# RK3566_USB_GPIO.net
KiCad netlist of a schematic drawn in Altium Designer
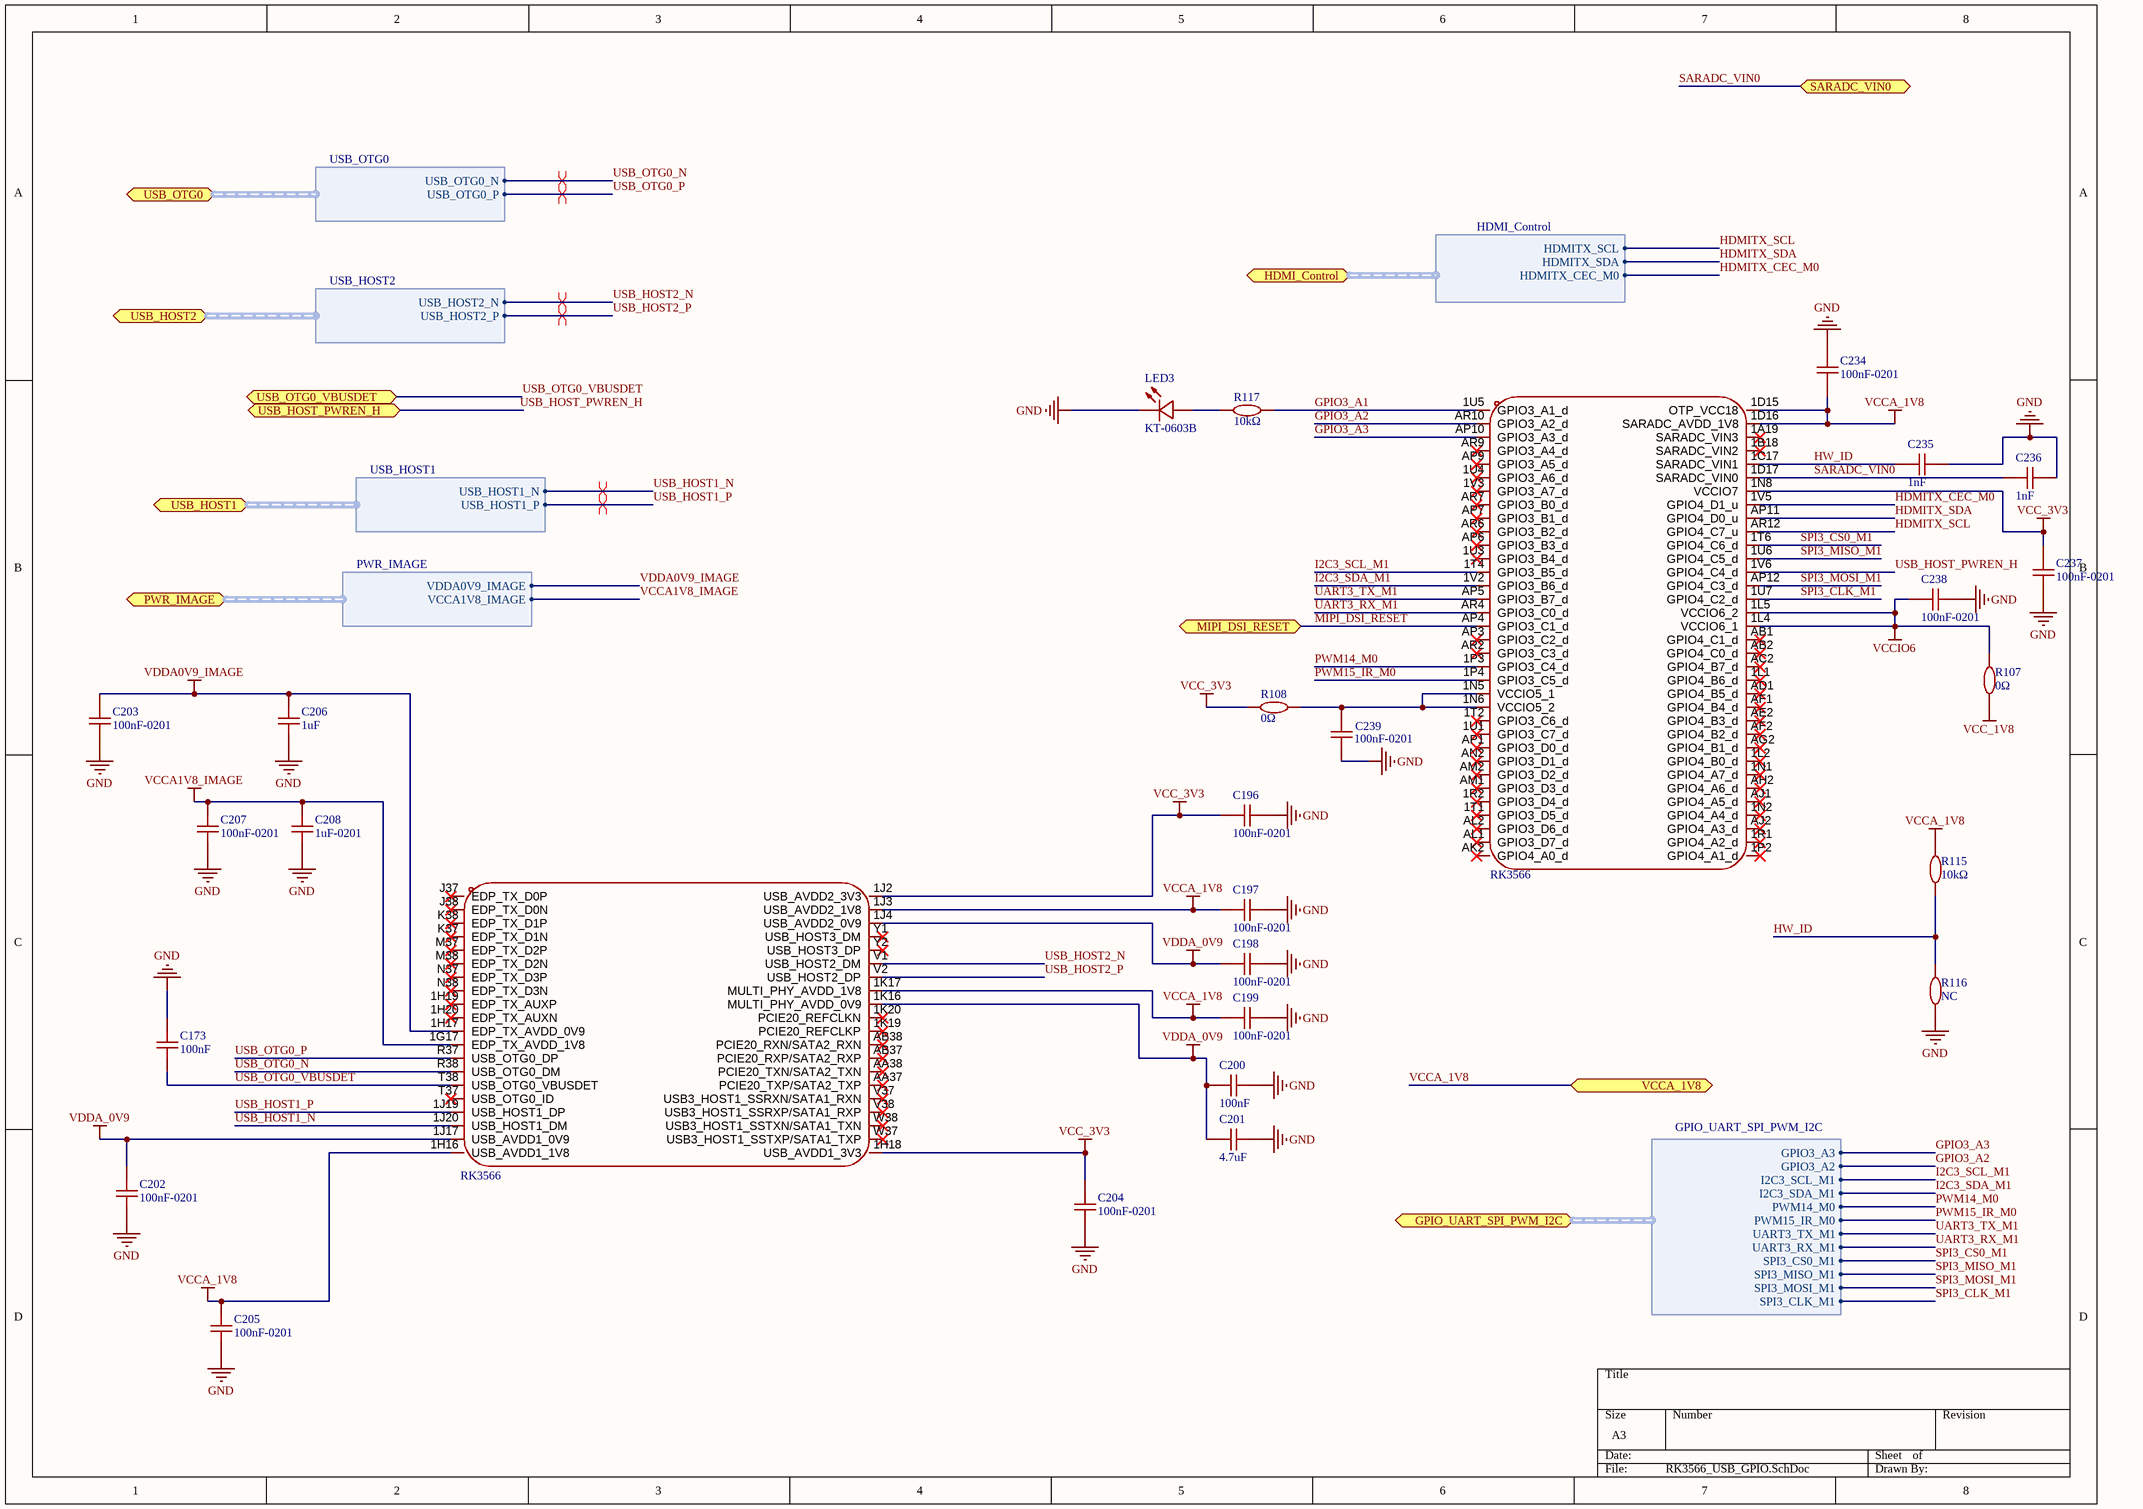
[diagram p0: RK3566_USB_GPIO.SchDoc]

(export (version "E")
  (design (tool "Eeschema 10.0.6"))
  (components
    (comp (ref "C173")
      (value "100nF")
      (footprint "C0402")
      (description "50V 100nF X7R ±10% 0402 Ceramic Capacitors ROHS")
      (libsource (lib "RLC") (part "100nF"))
    )
    (comp (ref "C196")
      (value "100nF-0201")
      (footprint "C0201")
      (description "CL03A104KO3NNNC")
      (libsource (lib "RLC") (part "100nF-0201"))
    )
    (comp (ref "C197")
      (value "100nF-0201")
      (footprint "C0201")
      (description "CL03A104KO3NNNC")
      (libsource (lib "RLC") (part "100nF-0201"))
    )
    (comp (ref "C198")
      (value "100nF-0201")
      (footprint "C0201")
      (description "CL03A104KO3NNNC")
      (libsource (lib "RLC") (part "100nF-0201"))
    )
    (comp (ref "C199")
      (value "100nF-0201")
      (footprint "C0201")
      (description "CL03A104KO3NNNC")
      (libsource (lib "RLC") (part "100nF-0201"))
    )
    (comp (ref "C200")
      (value "100nF")
      (footprint "C0402")
      (description "50V 100nF X7R ±10% 0402 Ceramic Capacitors ROHS")
      (libsource (lib "RLC") (part "100nF"))
    )
    (comp (ref "C201")
      (value "4.7uF")
      (footprint "C0402")
      (description "10V 4.7uF X5R ±20% 0402 Ceramic Capacitors ROHS")
      (libsource (lib "RLC") (part "4.7uF"))
    )
    (comp (ref "C202")
      (value "100nF-0201")
      (footprint "C0201")
      (description "CL03A104KO3NNNC")
      (libsource (lib "RLC") (part "100nF-0201"))
    )
    (comp (ref "C203")
      (value "100nF-0201")
      (footprint "C0201")
      (description "CL03A104KO3NNNC")
      (libsource (lib "RLC") (part "100nF-0201"))
    )
    (comp (ref "C204")
      (value "100nF-0201")
      (footprint "C0201")
      (description "CL03A104KO3NNNC")
      (libsource (lib "RLC") (part "100nF-0201"))
    )
    (comp (ref "C205")
      (value "100nF-0201")
      (footprint "C0201")
      (description "CL03A104KO3NNNC")
      (libsource (lib "RLC") (part "100nF-0201"))
    )
    (comp (ref "C206")
      (value "1uF")
      (footprint "C0402")
      (description "50V 1uF X5R ±10% 0402 Ceramic Capacitors ROHS")
      (libsource (lib "RLC") (part "1uF"))
    )
    (comp (ref "C207")
      (value "100nF-0201")
      (footprint "C0201")
      (description "CL03A104KO3NNNC")
      (libsource (lib "RLC") (part "100nF-0201"))
    )
    (comp (ref "C208")
      (value "1uF-0201")
      (footprint "C0201")
      (description "CL03A104KO3NNNC")
      (libsource (lib "RLC") (part "1uF-0201"))
    )
    (comp (ref "C234")
      (value "100nF-0201")
      (footprint "C0201")
      (description "CL03A104KO3NNNC")
      (libsource (lib "RLC") (part "100nF-0201"))
    )
    (comp (ref "C235")
      (value "1nF")
      (footprint "C0402")
      (description "50V 1nF X7R ±10% 0402 Ceramic Capacitors ROHS")
      (libsource (lib "RLC") (part "1nF"))
    )
    (comp (ref "C236")
      (value "1nF")
      (footprint "C0402")
      (description "50V 1nF X7R ±10% 0402 Ceramic Capacitors ROHS")
      (libsource (lib "RLC") (part "1nF"))
    )
    (comp (ref "C237")
      (value "100nF-0201")
      (footprint "C0201")
      (description "CL03A104KO3NNNC")
      (libsource (lib "RLC") (part "100nF-0201"))
    )
    (comp (ref "C238")
      (value "100nF-0201")
      (footprint "C0201")
      (description "CL03A104KO3NNNC")
      (libsource (lib "RLC") (part "100nF-0201"))
    )
    (comp (ref "C239")
      (value "100nF-0201")
      (footprint "C0201")
      (description "CL03A104KO3NNNC")
      (libsource (lib "RLC") (part "100nF-0201"))
    )
    (comp (ref "LED3")
      (value "KT-0603B")
      (footprint "LED0603-BL")
      (description "30mA 2.6V~3.2V Blue 0603 LED Indication - Discrete ROHS")
      (libsource (lib "LED") (part "KT-0603B"))
    )
    (comp (ref "R107")
      (value "0Ω")
      (footprint "R0402")
      (description "0Ω 62.5mW 50V Thick Film Resistor ±1% 0402 Chip Resistor - Surface Mount ROHS")
      (libsource (lib "RLC") (part "0Ω"))
    )
    (comp (ref "R108")
      (value "0Ω")
      (footprint "R0402")
      (description "0Ω 62.5mW 50V Thick Film Resistor ±1% 0402 Chip Resistor - Surface Mount ROHS")
      (libsource (lib "RLC") (part "0Ω"))
    )
    (comp (ref "R115")
      (value "10kΩ")
      (footprint "R0402")
      (description "62.5mW 10kΩ 50V ±100ppm/℃ Thick Film Resistor ±1% 0402 Chip Resistor - Surface Mount ROHS")
      (libsource (lib "RLC") (part "10kΩ"))
    )
    (comp (ref "R116")
      (value "NC")
      (footprint "R0402")
      (description "62.5mW 10kΩ 50V ±100ppm/℃ Thick Film Resistor ±1% 0402 Chip Resistor - Surface Mount ROHS")
      (libsource (lib "RLC") (part "10kΩ"))
    )
    (comp (ref "R117")
      (value "10kΩ")
      (footprint "R0402")
      (description "62.5mW 10kΩ 50V ±100ppm/℃ Thick Film Resistor ±1% 0402 Chip Resistor - Surface Mount ROHS")
      (libsource (lib "RLC") (part "10kΩ"))
    )
    (comp (ref "U2")
      (value "RK3566")
      (footprint "BGA-565_L15.5-W14.4-P0.40_RK3566_1")
      (description "BGA-565(15.5x14.4)")
      (libsource (lib "IC") (part "RK3566"))
    )
  )
  (nets
    (net (code "7") (name "/GPIO3_A1") (class "Default")
      (node (ref "R117") (pin "1") (pinfunction "1_1") (pintype "passive"))
      (node (ref "U2") (pin "1U5") (pinfunction "GPIO3_A1_d_1U5") (pintype "passive"))
    )
    (net (code "8") (name "/GPIO3_A2") (class "Default")
      (node (ref "U2") (pin "AR10") (pinfunction "GPIO3_A2_d_AR10") (pintype "passive"))
    )
    (net (code "9") (name "/GPIO3_A3") (class "Default")
      (node (ref "U2") (pin "AP10") (pinfunction "GPIO3_A3_d_AP10") (pintype "passive"))
    )
    (net (code "10") (name "/HDMITX_CEC_M0") (class "Default")
      (node (ref "U2") (pin "1V5") (pinfunction "GPIO4_D1_u_1V5") (pintype "passive"))
    )
    (net (code "11") (name "/HDMITX_SCL") (class "Default")
      (node (ref "U2") (pin "AR12") (pinfunction "GPIO4_C7_u_AR12") (pintype "passive"))
    )
    (net (code "12") (name "/HDMITX_SDA") (class "Default")
      (node (ref "U2") (pin "AP11") (pinfunction "GPIO4_D0_u_AP11") (pintype "passive"))
    )
    (net (code "13") (name "/HW_ID") (class "Default")
      (node (ref "C235") (pin "1") (pinfunction "1_1") (pintype "passive"))
      (node (ref "R115") (pin "1") (pinfunction "1_1") (pintype "passive"))
      (node (ref "R116") (pin "2") (pinfunction "2_2") (pintype "passive"))
      (node (ref "U2") (pin "1C17") (pinfunction "SARADC_VIN1_1C17") (pintype "passive"))
    )
    (net (code "14") (name "/I2C3_SCL_M1") (class "Default")
      (node (ref "U2") (pin "1T4") (pinfunction "GPIO3_B5_d_1T4") (pintype "passive"))
    )
    (net (code "15") (name "/I2C3_SDA_M1") (class "Default")
      (node (ref "U2") (pin "1V2") (pinfunction "GPIO3_B6_d_1V2") (pintype "passive"))
    )
    (net (code "16") (name "/MIPI_DSI_RESET") (class "Default")
      (node (ref "U2") (pin "AP4") (pinfunction "GPIO3_C1_d_AP4") (pintype "passive"))
    )
    (net (code "17") (name "/PWM14_M0") (class "Default")
      (node (ref "U2") (pin "1P3") (pinfunction "GPIO3_C4_d_1P3") (pintype "passive"))
    )
    (net (code "18") (name "/PWM15_IR_M0") (class "Default")
      (node (ref "U2") (pin "1P4") (pinfunction "GPIO3_C5_d_1P4") (pintype "passive"))
    )
    (net (code "19") (name "/SARADC_VIN0") (class "Default")
      (node (ref "C236") (pin "1") (pinfunction "1_1") (pintype "passive"))
      (node (ref "U2") (pin "1D17") (pinfunction "SARADC_VIN0_1D17") (pintype "passive"))
    )
    (net (code "20") (name "/SPI3_CLK_M1") (class "Default")
      (node (ref "U2") (pin "1U7") (pinfunction "GPIO4_C2_d_1U7") (pintype "passive"))
    )
    (net (code "21") (name "/SPI3_CS0_M1") (class "Default")
      (node (ref "U2") (pin "1T6") (pinfunction "GPIO4_C6_d_1T6") (pintype "passive"))
    )
    (net (code "22") (name "/SPI3_MISO_M1") (class "Default")
      (node (ref "U2") (pin "1U6") (pinfunction "GPIO4_C5_d_1U6") (pintype "passive"))
    )
    (net (code "23") (name "/SPI3_MOSI_M1") (class "Default")
      (node (ref "U2") (pin "AP12") (pinfunction "GPIO4_C3_d_AP12") (pintype "passive"))
    )
    (net (code "24") (name "/UART3_RX_M1") (class "Default")
      (node (ref "U2") (pin "AR4") (pinfunction "GPIO3_C0_d_AR4") (pintype "passive"))
    )
    (net (code "25") (name "/UART3_TX_M1") (class "Default")
      (node (ref "U2") (pin "AP5") (pinfunction "GPIO3_B7_d_AP5") (pintype "passive"))
    )
    (net (code "26") (name "/USB_HOST1_N") (class "Default")
      (node (ref "U2") (pin "1J20") (pinfunction "USB_HOST1_DM_1J20") (pintype "passive"))
    )
    (net (code "27") (name "/USB_HOST1_P") (class "Default")
      (node (ref "U2") (pin "1J19") (pinfunction "USB_HOST1_DP_1J19") (pintype "passive"))
    )
    (net (code "28") (name "/USB_HOST2_N") (class "Default")
      (node (ref "U2") (pin "V1") (pinfunction "USB_HOST2_DM_V1") (pintype "passive"))
    )
    (net (code "29") (name "/USB_HOST2_P") (class "Default")
      (node (ref "U2") (pin "V2") (pinfunction "USB_HOST2_DP_V2") (pintype "passive"))
    )
    (net (code "30") (name "/USB_HOST_PWREN_H") (class "Default")
      (node (ref "U2") (pin "1V6") (pinfunction "GPIO4_C4_d_1V6") (pintype "passive"))
    )
    (net (code "31") (name "/USB_OTG0_N") (class "Default")
      (node (ref "U2") (pin "R38") (pinfunction "USB_OTG0_DM_R38") (pintype "passive"))
    )
    (net (code "32") (name "/USB_OTG0_P") (class "Default")
      (node (ref "U2") (pin "R37") (pinfunction "USB_OTG0_DP_R37") (pintype "passive"))
    )
    (net (code "33") (name "/USB_OTG0_VBUSDET") (class "Default")
      (node (ref "C173") (pin "1") (pinfunction "1_1") (pintype "passive"))
      (node (ref "U2") (pin "T38") (pinfunction "USB_OTG0_VBUSDET_T38") (pintype "passive"))
    )
    (net (code "40") (name "GND") (class "Default")
      (node (ref "C173") (pin "2") (pinfunction "2_2") (pintype "passive"))
      (node (ref "C196") (pin "2") (pinfunction "2_2") (pintype "passive"))
      (node (ref "C197") (pin "2") (pinfunction "2_2") (pintype "passive"))
      (node (ref "C198") (pin "2") (pinfunction "2_2") (pintype "passive"))
      (node (ref "C199") (pin "2") (pinfunction "2_2") (pintype "passive"))
      (node (ref "C200") (pin "2") (pinfunction "2_2") (pintype "passive"))
      (node (ref "C201") (pin "2") (pinfunction "2_2") (pintype "passive"))
      (node (ref "C202") (pin "1") (pinfunction "1_1") (pintype "passive"))
      (node (ref "C203") (pin "1") (pinfunction "1_1") (pintype "passive"))
      (node (ref "C204") (pin "1") (pinfunction "1_1") (pintype "passive"))
      (node (ref "C205") (pin "1") (pinfunction "1_1") (pintype "passive"))
      (node (ref "C206") (pin "1") (pinfunction "1_1") (pintype "passive"))
      (node (ref "C207") (pin "1") (pinfunction "1_1") (pintype "passive"))
      (node (ref "C208") (pin "1") (pinfunction "1_1") (pintype "passive"))
      (node (ref "C234") (pin "1") (pinfunction "1_1") (pintype "passive"))
      (node (ref "C235") (pin "2") (pinfunction "2_2") (pintype "passive"))
      (node (ref "C236") (pin "2") (pinfunction "2_2") (pintype "passive"))
      (node (ref "C237") (pin "2") (pinfunction "2_2") (pintype "passive"))
      (node (ref "C238") (pin "2") (pinfunction "2_2") (pintype "passive"))
      (node (ref "C239") (pin "1") (pinfunction "1_1") (pintype "passive"))
      (node (ref "LED3") (pin "1") (pinfunction "K_1") (pintype "passive"))
      (node (ref "R116") (pin "1") (pinfunction "1_1") (pintype "passive"))
    )
    (net (code "41") (name "Net-(LED3-A)") (class "Default")
      (node (ref "LED3") (pin "2") (pinfunction "A_2") (pintype "passive"))
      (node (ref "R117") (pin "2") (pinfunction "2_2") (pintype "passive"))
    )
    (net (code "42") (name "Net-(U2F-VCCIO5_1)") (class "Default")
      (node (ref "C239") (pin "2") (pinfunction "2_2") (pintype "passive"))
      (node (ref "R108") (pin "2") (pinfunction "2_2") (pintype "passive"))
      (node (ref "U2") (pin "1N5") (pinfunction "VCCIO5_1_1N5") (pintype "passive"))
      (node (ref "U2") (pin "1N6") (pinfunction "VCCIO5_2_1N6") (pintype "passive"))
    )
    (net (code "43") (name "VCCA1V8_IMAGE") (class "Default")
      (node (ref "C207") (pin "2") (pinfunction "2_2") (pintype "passive"))
      (node (ref "C208") (pin "2") (pinfunction "2_2") (pintype "passive"))
      (node (ref "U2") (pin "1G17") (pinfunction "EDP_TX_AVDD_1V8_1G17") (pintype "passive"))
    )
    (net (code "44") (name "VCCA_1V8") (class "Default")
      (node (ref "C197") (pin "1") (pinfunction "1_1") (pintype "passive"))
      (node (ref "C199") (pin "1") (pinfunction "1_1") (pintype "passive"))
      (node (ref "C205") (pin "2") (pinfunction "2_2") (pintype "passive"))
      (node (ref "C234") (pin "2") (pinfunction "2_2") (pintype "passive"))
      (node (ref "R115") (pin "2") (pinfunction "2_2") (pintype "passive"))
      (node (ref "U2") (pin "1D15") (pinfunction "OTP_VCC18_1D15") (pintype "passive"))
      (node (ref "U2") (pin "1D16") (pinfunction "SARADC_AVDD_1V8_1D16") (pintype "passive"))
      (node (ref "U2") (pin "1H16") (pinfunction "USB_AVDD1_1V8_1H16") (pintype "passive"))
      (node (ref "U2") (pin "1J3") (pinfunction "USB_AVDD2_1V8_1J3") (pintype "passive"))
      (node (ref "U2") (pin "1K17") (pinfunction "MULTI_PHY_AVDD_1V8_1K17") (pintype "passive"))
    )
    (net (code "45") (name "VCCIO6") (class "Default")
      (node (ref "C238") (pin "1") (pinfunction "1_1") (pintype "passive"))
      (node (ref "R107") (pin "2") (pinfunction "2_2") (pintype "passive"))
      (node (ref "U2") (pin "1L4") (pinfunction "VCCIO6_1_1L4") (pintype "passive"))
      (node (ref "U2") (pin "1L5") (pinfunction "VCCIO6_2_1L5") (pintype "passive"))
    )
    (net (code "46") (name "VCC_1V8") (class "Default")
      (node (ref "R107") (pin "1") (pinfunction "1_1") (pintype "passive"))
    )
    (net (code "47") (name "VCC_3V3") (class "Default")
      (node (ref "C196") (pin "1") (pinfunction "1_1") (pintype "passive"))
      (node (ref "C204") (pin "2") (pinfunction "2_2") (pintype "passive"))
      (node (ref "C237") (pin "1") (pinfunction "1_1") (pintype "passive"))
      (node (ref "R108") (pin "1") (pinfunction "1_1") (pintype "passive"))
      (node (ref "U2") (pin "1H18") (pinfunction "USB_AVDD1_3V3_1H18") (pintype "passive"))
      (node (ref "U2") (pin "1J2") (pinfunction "USB_AVDD2_3V3_1J2") (pintype "passive"))
      (node (ref "U2") (pin "1N8") (pinfunction "VCCIO7_1N8") (pintype "passive"))
    )
    (net (code "48") (name "VDDA0V9_IMAGE") (class "Default")
      (node (ref "C203") (pin "2") (pinfunction "2_2") (pintype "passive"))
      (node (ref "C206") (pin "2") (pinfunction "2_2") (pintype "passive"))
      (node (ref "U2") (pin "1H17") (pinfunction "EDP_TX_AVDD_0V9_1H17") (pintype "passive"))
    )
    (net (code "49") (name "VDDA_0V9") (class "Default")
      (node (ref "C198") (pin "1") (pinfunction "1_1") (pintype "passive"))
      (node (ref "C200") (pin "1") (pinfunction "1_1") (pintype "passive"))
      (node (ref "C201") (pin "1") (pinfunction "1_1") (pintype "passive"))
      (node (ref "C202") (pin "2") (pinfunction "2_2") (pintype "passive"))
      (node (ref "U2") (pin "1J17") (pinfunction "USB_AVDD1_0V9_1J17") (pintype "passive"))
      (node (ref "U2") (pin "1J4") (pinfunction "USB_AVDD2_0V9_1J4") (pintype "passive"))
      (node (ref "U2") (pin "1K16") (pinfunction "MULTI_PHY_AVDD_0V9_1K16") (pintype "passive"))
    )
    (net (code "50") (name "unconnected-(U2F-GPIO3_A4_d-PadAR9)") (class "Default")
      (node (ref "U2") (pin "AR9") (pinfunction "GPIO3_A4_d_AR9") (pintype "passive+no_connect"))
    )
    (net (code "51") (name "unconnected-(U2F-GPIO3_A5_d-PadAP9)") (class "Default")
      (node (ref "U2") (pin "AP9") (pinfunction "GPIO3_A5_d_AP9") (pintype "passive+no_connect"))
    )
    (net (code "52") (name "unconnected-(U2F-GPIO3_A6_d-Pad1U4)") (class "Default")
      (node (ref "U2") (pin "1U4") (pinfunction "GPIO3_A6_d_1U4") (pintype "passive+no_connect"))
    )
    (net (code "53") (name "unconnected-(U2F-GPIO3_A7_d-Pad1V3)") (class "Default")
      (node (ref "U2") (pin "1V3") (pinfunction "GPIO3_A7_d_1V3") (pintype "passive+no_connect"))
    )
    (net (code "54") (name "unconnected-(U2F-GPIO3_B0_d-PadAR7)") (class "Default")
      (node (ref "U2") (pin "AR7") (pinfunction "GPIO3_B0_d_AR7") (pintype "passive+no_connect"))
    )
    (net (code "55") (name "unconnected-(U2F-GPIO3_B1_d-PadAP7)") (class "Default")
      (node (ref "U2") (pin "AP7") (pinfunction "GPIO3_B1_d_AP7") (pintype "passive+no_connect"))
    )
    (net (code "56") (name "unconnected-(U2F-GPIO3_B2_d-PadAR6)") (class "Default")
      (node (ref "U2") (pin "AR6") (pinfunction "GPIO3_B2_d_AR6") (pintype "passive+no_connect"))
    )
    (net (code "57") (name "unconnected-(U2F-GPIO3_B3_d-PadAP6)") (class "Default")
      (node (ref "U2") (pin "AP6") (pinfunction "GPIO3_B3_d_AP6") (pintype "passive+no_connect"))
    )
    (net (code "58") (name "unconnected-(U2F-GPIO3_B4_d-Pad1U3)") (class "Default")
      (node (ref "U2") (pin "1U3") (pinfunction "GPIO3_B4_d_1U3") (pintype "passive+no_connect"))
    )
    (net (code "59") (name "unconnected-(U2F-GPIO3_C2_d-PadAP3)") (class "Default")
      (node (ref "U2") (pin "AP3") (pinfunction "GPIO3_C2_d_AP3") (pintype "passive+no_connect"))
    )
    (net (code "60") (name "unconnected-(U2F-GPIO3_C3_d-PadAR2)") (class "Default")
      (node (ref "U2") (pin "AR2") (pinfunction "GPIO3_C3_d_AR2") (pintype "passive+no_connect"))
    )
    (net (code "61") (name "unconnected-(U2F-GPIO3_C6_d-Pad1T2)") (class "Default")
      (node (ref "U2") (pin "1T2") (pinfunction "GPIO3_C6_d_1T2") (pintype "passive+no_connect"))
    )
    (net (code "62") (name "unconnected-(U2F-GPIO3_C7_d-Pad1U1)") (class "Default")
      (node (ref "U2") (pin "1U1") (pinfunction "GPIO3_C7_d_1U1") (pintype "passive+no_connect"))
    )
    (net (code "63") (name "unconnected-(U2F-GPIO3_D0_d-PadAP1)") (class "Default")
      (node (ref "U2") (pin "AP1") (pinfunction "GPIO3_D0_d_AP1") (pintype "passive+no_connect"))
    )
    (net (code "64") (name "unconnected-(U2F-GPIO3_D1_d-PadAN2)") (class "Default")
      (node (ref "U2") (pin "AN2") (pinfunction "GPIO3_D1_d_AN2") (pintype "passive+no_connect"))
    )
    (net (code "65") (name "unconnected-(U2F-GPIO3_D2_d-PadAM2)") (class "Default")
      (node (ref "U2") (pin "AM2") (pinfunction "GPIO3_D2_d_AM2") (pintype "passive+no_connect"))
    )
    (net (code "66") (name "unconnected-(U2F-GPIO3_D3_d-PadAM1)") (class "Default")
      (node (ref "U2") (pin "AM1") (pinfunction "GPIO3_D3_d_AM1") (pintype "passive+no_connect"))
    )
    (net (code "67") (name "unconnected-(U2F-GPIO3_D4_d-Pad1R2)") (class "Default")
      (node (ref "U2") (pin "1R2") (pinfunction "GPIO3_D4_d_1R2") (pintype "passive+no_connect"))
    )
    (net (code "68") (name "unconnected-(U2F-GPIO3_D5_d-Pad1T1)") (class "Default")
      (node (ref "U2") (pin "1T1") (pinfunction "GPIO3_D5_d_1T1") (pintype "passive+no_connect"))
    )
    (net (code "69") (name "unconnected-(U2F-GPIO3_D6_d-PadAL2)") (class "Default")
      (node (ref "U2") (pin "AL2") (pinfunction "GPIO3_D6_d_AL2") (pintype "passive+no_connect"))
    )
    (net (code "70") (name "unconnected-(U2F-GPIO3_D7_d-PadAL1)") (class "Default")
      (node (ref "U2") (pin "AL1") (pinfunction "GPIO3_D7_d_AL1") (pintype "passive+no_connect"))
    )
    (net (code "71") (name "unconnected-(U2F-GPIO4_A0_d-PadAK2)") (class "Default")
      (node (ref "U2") (pin "AK2") (pinfunction "GPIO4_A0_d_AK2") (pintype "passive+no_connect"))
    )
    (net (code "72") (name "unconnected-(U2F-GPIO4_A1_d-Pad1P2)") (class "Default")
      (node (ref "U2") (pin "1P2") (pinfunction "GPIO4_A1_d_1P2") (pintype "passive+no_connect"))
    )
    (net (code "73") (name "unconnected-(U2F-GPIO4_A2_d-Pad1R1)") (class "Default")
      (node (ref "U2") (pin "1R1") (pinfunction "GPIO4_A2_d_1R1") (pintype "passive+no_connect"))
    )
    (net (code "74") (name "unconnected-(U2F-GPIO4_A3_d-PadAJ2)") (class "Default")
      (node (ref "U2") (pin "AJ2") (pinfunction "GPIO4_A3_d_AJ2") (pintype "passive+no_connect"))
    )
    (net (code "75") (name "unconnected-(U2F-GPIO4_A4_d-Pad1N2)") (class "Default")
      (node (ref "U2") (pin "1N2") (pinfunction "GPIO4_A4_d_1N2") (pintype "passive+no_connect"))
    )
    (net (code "76") (name "unconnected-(U2F-GPIO4_A5_d-PadAJ1)") (class "Default")
      (node (ref "U2") (pin "AJ1") (pinfunction "GPIO4_A5_d_AJ1") (pintype "passive+no_connect"))
    )
    (net (code "77") (name "unconnected-(U2F-GPIO4_A6_d-PadAH2)") (class "Default")
      (node (ref "U2") (pin "AH2") (pinfunction "GPIO4_A6_d_AH2") (pintype "passive+no_connect"))
    )
    (net (code "78") (name "unconnected-(U2F-GPIO4_A7_d-Pad1N1)") (class "Default")
      (node (ref "U2") (pin "1N1") (pinfunction "GPIO4_A7_d_1N1") (pintype "passive+no_connect"))
    )
    (net (code "79") (name "unconnected-(U2F-GPIO4_B0_d-Pad1L2)") (class "Default")
      (node (ref "U2") (pin "1L2") (pinfunction "GPIO4_B0_d_1L2") (pintype "passive+no_connect"))
    )
    (net (code "80") (name "unconnected-(U2F-GPIO4_B1_d-PadAG2)") (class "Default")
      (node (ref "U2") (pin "AG2") (pinfunction "GPIO4_B1_d_AG2") (pintype "passive+no_connect"))
    )
    (net (code "81") (name "unconnected-(U2F-GPIO4_B2_d-PadAF2)") (class "Default")
      (node (ref "U2") (pin "AF2") (pinfunction "GPIO4_B2_d_AF2") (pintype "passive+no_connect"))
    )
    (net (code "82") (name "unconnected-(U2F-GPIO4_B3_d-PadAE2)") (class "Default")
      (node (ref "U2") (pin "AE2") (pinfunction "GPIO4_B3_d_AE2") (pintype "passive+no_connect"))
    )
    (net (code "83") (name "unconnected-(U2F-GPIO4_B4_d-PadAF1)") (class "Default")
      (node (ref "U2") (pin "AF1") (pinfunction "GPIO4_B4_d_AF1") (pintype "passive+no_connect"))
    )
    (net (code "84") (name "unconnected-(U2F-GPIO4_B5_d-PadAD1)") (class "Default")
      (node (ref "U2") (pin "AD1") (pinfunction "GPIO4_B5_d_AD1") (pintype "passive+no_connect"))
    )
    (net (code "85") (name "unconnected-(U2F-GPIO4_B6_d-Pad1L1)") (class "Default")
      (node (ref "U2") (pin "1L1") (pinfunction "GPIO4_B6_d_1L1") (pintype "passive+no_connect"))
    )
    (net (code "86") (name "unconnected-(U2F-GPIO4_B7_d-PadAC2)") (class "Default")
      (node (ref "U2") (pin "AC2") (pinfunction "GPIO4_B7_d_AC2") (pintype "passive+no_connect"))
    )
    (net (code "87") (name "unconnected-(U2F-GPIO4_C0_d-PadAB2)") (class "Default")
      (node (ref "U2") (pin "AB2") (pinfunction "GPIO4_C0_d_AB2") (pintype "passive+no_connect"))
    )
    (net (code "88") (name "unconnected-(U2F-GPIO4_C1_d-PadAB1)") (class "Default")
      (node (ref "U2") (pin "AB1") (pinfunction "GPIO4_C1_d_AB1") (pintype "passive+no_connect"))
    )
    (net (code "89") (name "unconnected-(U2F-SARADC_VIN2-Pad1B18)") (class "Default")
      (node (ref "U2") (pin "1B18") (pinfunction "SARADC_VIN2_1B18") (pintype "passive+no_connect"))
    )
    (net (code "90") (name "unconnected-(U2F-SARADC_VIN3-Pad1A19)") (class "Default")
      (node (ref "U2") (pin "1A19") (pinfunction "SARADC_VIN3_1A19") (pintype "passive+no_connect"))
    )
    (net (code "91") (name "unconnected-(U2H-EDP_TX_AUXN-Pad1H20)") (class "Default")
      (node (ref "U2") (pin "1H20") (pinfunction "EDP_TX_AUXN_1H20") (pintype "passive+no_connect"))
    )
    (net (code "92") (name "unconnected-(U2H-EDP_TX_AUXP-Pad1H19)") (class "Default")
      (node (ref "U2") (pin "1H19") (pinfunction "EDP_TX_AUXP_1H19") (pintype "passive+no_connect"))
    )
    (net (code "93") (name "unconnected-(U2H-EDP_TX_D0N-PadJ38)") (class "Default")
      (node (ref "U2") (pin "J38") (pinfunction "EDP_TX_D0N_J38") (pintype "passive+no_connect"))
    )
    (net (code "94") (name "unconnected-(U2H-EDP_TX_D0P-PadJ37)") (class "Default")
      (node (ref "U2") (pin "J37") (pinfunction "EDP_TX_D0P_J37") (pintype "passive+no_connect"))
    )
    (net (code "95") (name "unconnected-(U2H-EDP_TX_D1N-PadK37)") (class "Default")
      (node (ref "U2") (pin "K37") (pinfunction "EDP_TX_D1N_K37") (pintype "passive+no_connect"))
    )
    (net (code "96") (name "unconnected-(U2H-EDP_TX_D1P-PadK38)") (class "Default")
      (node (ref "U2") (pin "K38") (pinfunction "EDP_TX_D1P_K38") (pintype "passive+no_connect"))
    )
    (net (code "97") (name "unconnected-(U2H-EDP_TX_D2N-PadM38)") (class "Default")
      (node (ref "U2") (pin "M38") (pinfunction "EDP_TX_D2N_M38") (pintype "passive+no_connect"))
    )
    (net (code "98") (name "unconnected-(U2H-EDP_TX_D2P-PadM37)") (class "Default")
      (node (ref "U2") (pin "M37") (pinfunction "EDP_TX_D2P_M37") (pintype "passive+no_connect"))
    )
    (net (code "99") (name "unconnected-(U2H-EDP_TX_D3N-PadN38)") (class "Default")
      (node (ref "U2") (pin "N38") (pinfunction "EDP_TX_D3N_N38") (pintype "passive+no_connect"))
    )
    (net (code "100") (name "unconnected-(U2H-EDP_TX_D3P-PadN37)") (class "Default")
      (node (ref "U2") (pin "N37") (pinfunction "EDP_TX_D3P_N37") (pintype "passive+no_connect"))
    )
    (net (code "101") (name "unconnected-(U2H-PCIE20_REFCLKN-Pad1K20)") (class "Default")
      (node (ref "U2") (pin "1K20") (pinfunction "PCIE20_REFCLKN_1K20") (pintype "passive+no_connect"))
    )
    (net (code "102") (name "unconnected-(U2H-PCIE20_REFCLKP-Pad1K19)") (class "Default")
      (node (ref "U2") (pin "1K19") (pinfunction "PCIE20_REFCLKP_1K19") (pintype "passive+no_connect"))
    )
    (net (code "103") (name "unconnected-(U2H-PCIE20_RXN{slash}SATA2_RXN-PadAB38)") (class "Default")
      (node (ref "U2") (pin "AB38") (pinfunction "PCIE20_RXN/SATA2_RXN_AB38") (pintype "passive+no_connect"))
    )
    (net (code "104") (name "unconnected-(U2H-PCIE20_RXP{slash}SATA2_RXP-PadAB37)") (class "Default")
      (node (ref "U2") (pin "AB37") (pinfunction "PCIE20_RXP/SATA2_RXP_AB37") (pintype "passive+no_connect"))
    )
    (net (code "105") (name "unconnected-(U2H-PCIE20_TXN{slash}SATA2_TXN-PadAA38)") (class "Default")
      (node (ref "U2") (pin "AA38") (pinfunction "PCIE20_TXN/SATA2_TXN_AA38") (pintype "passive+no_connect"))
    )
    (net (code "106") (name "unconnected-(U2H-PCIE20_TXP{slash}SATA2_TXP-PadAA37)") (class "Default")
      (node (ref "U2") (pin "AA37") (pinfunction "PCIE20_TXP/SATA2_TXP_AA37") (pintype "passive+no_connect"))
    )
    (net (code "107") (name "unconnected-(U2H-USB3_HOST1_SSRXN{slash}SATA1_RXN-PadV37)") (class "Default")
      (node (ref "U2") (pin "V37") (pinfunction "USB3_HOST1_SSRXN/SATA1_RXN_V37") (pintype "passive+no_connect"))
    )
    (net (code "108") (name "unconnected-(U2H-USB3_HOST1_SSRXP{slash}SATA1_RXP-PadV38)") (class "Default")
      (node (ref "U2") (pin "V38") (pinfunction "USB3_HOST1_SSRXP/SATA1_RXP_V38") (pintype "passive+no_connect"))
    )
    (net (code "109") (name "unconnected-(U2H-USB3_HOST1_SSTXN{slash}SATA1_TXN-PadW38)") (class "Default")
      (node (ref "U2") (pin "W38") (pinfunction "USB3_HOST1_SSTXN/SATA1_TXN_W38") (pintype "passive+no_connect"))
    )
    (net (code "110") (name "unconnected-(U2H-USB3_HOST1_SSTXP{slash}SATA1_TXP-PadW37)") (class "Default")
      (node (ref "U2") (pin "W37") (pinfunction "USB3_HOST1_SSTXP/SATA1_TXP_W37") (pintype "passive+no_connect"))
    )
    (net (code "111") (name "unconnected-(U2H-USB_HOST3_DM-PadY1)") (class "Default")
      (node (ref "U2") (pin "Y1") (pinfunction "USB_HOST3_DM_Y1") (pintype "passive+no_connect"))
    )
    (net (code "112") (name "unconnected-(U2H-USB_HOST3_DP-PadY2)") (class "Default")
      (node (ref "U2") (pin "Y2") (pinfunction "USB_HOST3_DP_Y2") (pintype "passive+no_connect"))
    )
    (net (code "113") (name "unconnected-(U2H-USB_OTG0_ID-PadT37)") (class "Default")
      (node (ref "U2") (pin "T37") (pinfunction "USB_OTG0_ID_T37") (pintype "passive+no_connect"))
    )
  )
)
